# 2-MCU.net
KiCad netlist of a schematic drawn in Altium Designer
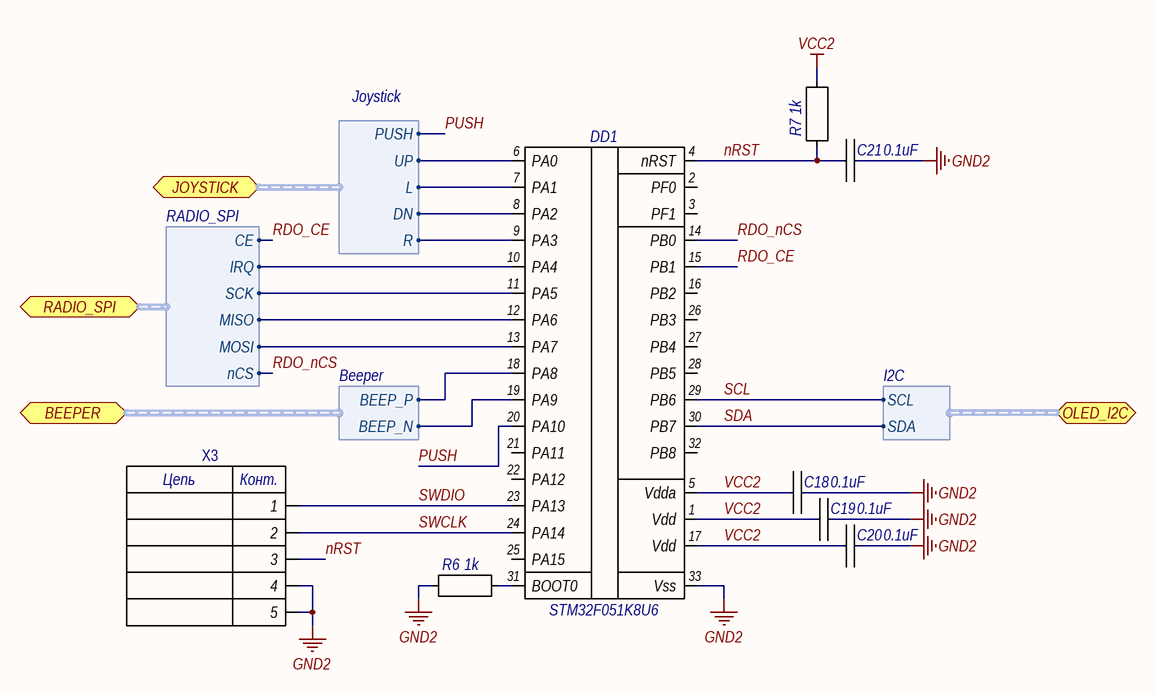
[diagram p0: 2-MCU.SchDoc]

(export (version "E")
  (design (tool "Eeschema 10.0.6"))
  (components
    (comp (ref "C18")
      (value "0.1uF")
      (footprint "CHIP_0402_C")
      (description "Конденсатор")
      (fields (field (name "PARTNUMBER") "CC0402KRX7R7BB104") (field (name "MFG") "YAGEO"))
      (libsource (lib "RCL") (part "Конденсатор"))
    )
    (comp (ref "C19")
      (value "0.1uF")
      (footprint "CHIP_0402_C")
      (description "Конденсатор")
      (fields (field (name "PARTNUMBER") "CC0402KRX7R7BB104") (field (name "MFG") "YAGEO"))
      (libsource (lib "RCL") (part "Конденсатор"))
    )
    (comp (ref "C20")
      (value "0.1uF")
      (footprint "CHIP_0402_C")
      (description "Конденсатор")
      (fields (field (name "PARTNUMBER") "CC0402KRX7R7BB104") (field (name "MFG") "YAGEO"))
      (libsource (lib "RCL") (part "Конденсатор"))
    )
    (comp (ref "C21")
      (value "0.1uF")
      (footprint "CHIP_0402_C")
      (description "Конденсатор")
      (fields (field (name "PARTNUMBER") "CC0402KRX7R7BB104") (field (name "MFG") "YAGEO"))
      (libsource (lib "RCL") (part "Конденсатор"))
    )
    (comp (ref "DD1")
      (value "STM32F0xx_32")
      (footprint "UFQFPN32")
      (description "MCU, 32-leaded")
      (fields (field (name "PARTNUMBER") "STM32F051K8U6") (field (name "MFG") "ST"))
      (libsource (lib "ic") (part "STM32F0xx_32"))
    )
    (comp (ref "R6")
      (value "1k")
      (footprint "CHIP_0402_R")
      (description "Резистор")
      (fields (field (name "PARTNUMBER") "RC0402FR-071KL") (field (name "MFG") "YAGEO"))
      (libsource (lib "RCL") (part "Резистор"))
    )
    (comp (ref "R7")
      (value "1k")
      (footprint "CHIP_0402_R")
      (description "Резистор")
      (fields (field (name "PARTNUMBER") "RC0402FR-071KL") (field (name "MFG") "YAGEO"))
      (libsource (lib "RCL") (part "Резистор"))
    )
    (comp (ref "X3")
      (value "SWD for STM32")
      (footprint "STM32 SWD-4")
      (description "Конт. площадки для подключения SWD")
      (libsource (lib "conn") (part "SWD_STM32"))
    )
  )
  (nets
    (net (code "5") (name "/BEEP_N") (class "Default")
      (node (ref "DD1") (pin "19") (pinfunction "PA9_19") (pintype "passive"))
    )
    (net (code "6") (name "/BEEP_P") (class "Default")
      (node (ref "DD1") (pin "18") (pinfunction "PA8_18") (pintype "passive"))
    )
    (net (code "7") (name "/DN") (class "Default")
      (node (ref "DD1") (pin "8") (pinfunction "PA2_8") (pintype "passive"))
    )
    (net (code "8") (name "/IRQ") (class "Default")
      (node (ref "DD1") (pin "10") (pinfunction "PA4_10") (pintype "passive"))
    )
    (net (code "9") (name "/L") (class "Default")
      (node (ref "DD1") (pin "7") (pinfunction "PA1_7") (pintype "passive"))
    )
    (net (code "10") (name "/MISO") (class "Default")
      (node (ref "DD1") (pin "12") (pinfunction "PA6_12") (pintype "passive"))
    )
    (net (code "11") (name "/MOSI") (class "Default")
      (node (ref "DD1") (pin "13") (pinfunction "PA7_13") (pintype "passive"))
    )
    (net (code "12") (name "/PUSH") (class "Default")
      (node (ref "DD1") (pin "20") (pinfunction "PA10_20") (pintype "passive"))
    )
    (net (code "13") (name "/R") (class "Default")
      (node (ref "DD1") (pin "9") (pinfunction "PA3_9") (pintype "passive"))
    )
    (net (code "14") (name "/RDO_CE") (class "Default")
      (node (ref "DD1") (pin "15") (pinfunction "PB1_15") (pintype "passive"))
    )
    (net (code "15") (name "/RDO_nCS") (class "Default")
      (node (ref "DD1") (pin "14") (pinfunction "PB0_14") (pintype "passive"))
    )
    (net (code "16") (name "/SCK") (class "Default")
      (node (ref "DD1") (pin "11") (pinfunction "PA5_11") (pintype "passive"))
    )
    (net (code "17") (name "/SCL") (class "Default")
      (node (ref "DD1") (pin "29") (pinfunction "PB6_29") (pintype "passive"))
    )
    (net (code "18") (name "/SDA") (class "Default")
      (node (ref "DD1") (pin "30") (pinfunction "PB7_30") (pintype "passive"))
    )
    (net (code "19") (name "/SWCLK") (class "Default")
      (node (ref "DD1") (pin "24") (pinfunction "PA14_24") (pintype "passive"))
      (node (ref "X3") (pin "2") (pinfunction "2_2") (pintype "passive"))
    )
    (net (code "20") (name "/SWDIO") (class "Default")
      (node (ref "DD1") (pin "23") (pinfunction "PA13_23") (pintype "passive"))
      (node (ref "X3") (pin "1") (pinfunction "1_1") (pintype "passive"))
    )
    (net (code "21") (name "/UP") (class "Default")
      (node (ref "DD1") (pin "6") (pinfunction "PA0_6") (pintype "passive"))
    )
    (net (code "22") (name "/nRST") (class "Default")
      (node (ref "C21") (pin "2") (pinfunction "2_2") (pintype "passive"))
      (node (ref "DD1") (pin "4") (pinfunction "nRST_4") (pintype "passive"))
      (node (ref "R7") (pin "1") (pinfunction "1_1") (pintype "passive"))
      (node (ref "X3") (pin "3") (pinfunction "3_3") (pintype "passive"))
    )
    (net (code "27") (name "GND2") (class "Default")
      (node (ref "C18") (pin "1") (pinfunction "1_1") (pintype "passive"))
      (node (ref "C19") (pin "1") (pinfunction "1_1") (pintype "passive"))
      (node (ref "C20") (pin "1") (pinfunction "1_1") (pintype "passive"))
      (node (ref "C21") (pin "1") (pinfunction "1_1") (pintype "passive"))
      (node (ref "DD1") (pin "33") (pinfunction "Vss_33") (pintype "passive"))
      (node (ref "R6") (pin "1") (pinfunction "1_1") (pintype "passive"))
      (node (ref "X3") (pin "4") (pinfunction "4_4") (pintype "passive"))
      (node (ref "X3") (pin "5") (pinfunction "5_5") (pintype "passive"))
    )
    (net (code "28") (name "Net-(DD1-BOOT0)") (class "Default")
      (node (ref "DD1") (pin "31") (pinfunction "BOOT0_31") (pintype "passive"))
      (node (ref "R6") (pin "2") (pinfunction "2_2") (pintype "passive"))
    )
    (net (code "29") (name "VCC2") (class "Default")
      (node (ref "C18") (pin "2") (pinfunction "2_2") (pintype "passive"))
      (node (ref "C19") (pin "2") (pinfunction "2_2") (pintype "passive"))
      (node (ref "C20") (pin "2") (pinfunction "2_2") (pintype "passive"))
      (node (ref "DD1") (pin "1") (pinfunction "Vdd_1") (pintype "passive"))
      (node (ref "DD1") (pin "17") (pinfunction "Vdd_17") (pintype "passive"))
      (node (ref "DD1") (pin "5") (pinfunction "Vdda_5") (pintype "passive"))
      (node (ref "R7") (pin "2") (pinfunction "2_2") (pintype "passive"))
    )
    (net (code "30") (name "unconnected-(DD1-PA11-Pad21)") (class "Default")
      (node (ref "DD1") (pin "21") (pinfunction "PA11_21") (pintype "passive"))
    )
    (net (code "31") (name "unconnected-(DD1-PA12-Pad22)") (class "Default")
      (node (ref "DD1") (pin "22") (pinfunction "PA12_22") (pintype "passive"))
    )
    (net (code "32") (name "unconnected-(DD1-PA15-Pad25)") (class "Default")
      (node (ref "DD1") (pin "25") (pinfunction "PA15_25") (pintype "passive"))
    )
    (net (code "33") (name "unconnected-(DD1-PB2-Pad16)") (class "Default")
      (node (ref "DD1") (pin "16") (pinfunction "PB2_16") (pintype "passive"))
    )
    (net (code "34") (name "unconnected-(DD1-PB3-Pad26)") (class "Default")
      (node (ref "DD1") (pin "26") (pinfunction "PB3_26") (pintype "passive"))
    )
    (net (code "35") (name "unconnected-(DD1-PB4-Pad27)") (class "Default")
      (node (ref "DD1") (pin "27") (pinfunction "PB4_27") (pintype "passive"))
    )
    (net (code "36") (name "unconnected-(DD1-PB5-Pad28)") (class "Default")
      (node (ref "DD1") (pin "28") (pinfunction "PB5_28") (pintype "passive"))
    )
    (net (code "37") (name "unconnected-(DD1-PB8-Pad32)") (class "Default")
      (node (ref "DD1") (pin "32") (pinfunction "PB8_32") (pintype "passive"))
    )
    (net (code "38") (name "unconnected-(DD1-PF0-Pad2)") (class "Default")
      (node (ref "DD1") (pin "2") (pinfunction "PF0_2") (pintype "passive"))
    )
    (net (code "39") (name "unconnected-(DD1-PF1-Pad3)") (class "Default")
      (node (ref "DD1") (pin "3") (pinfunction "PF1_3") (pintype "passive"))
    )
  )
)
